# SCH_CentralkaPawela-1_3_2025-06-29.net
KiCad netlist of a schematic drawn in EasyEDA
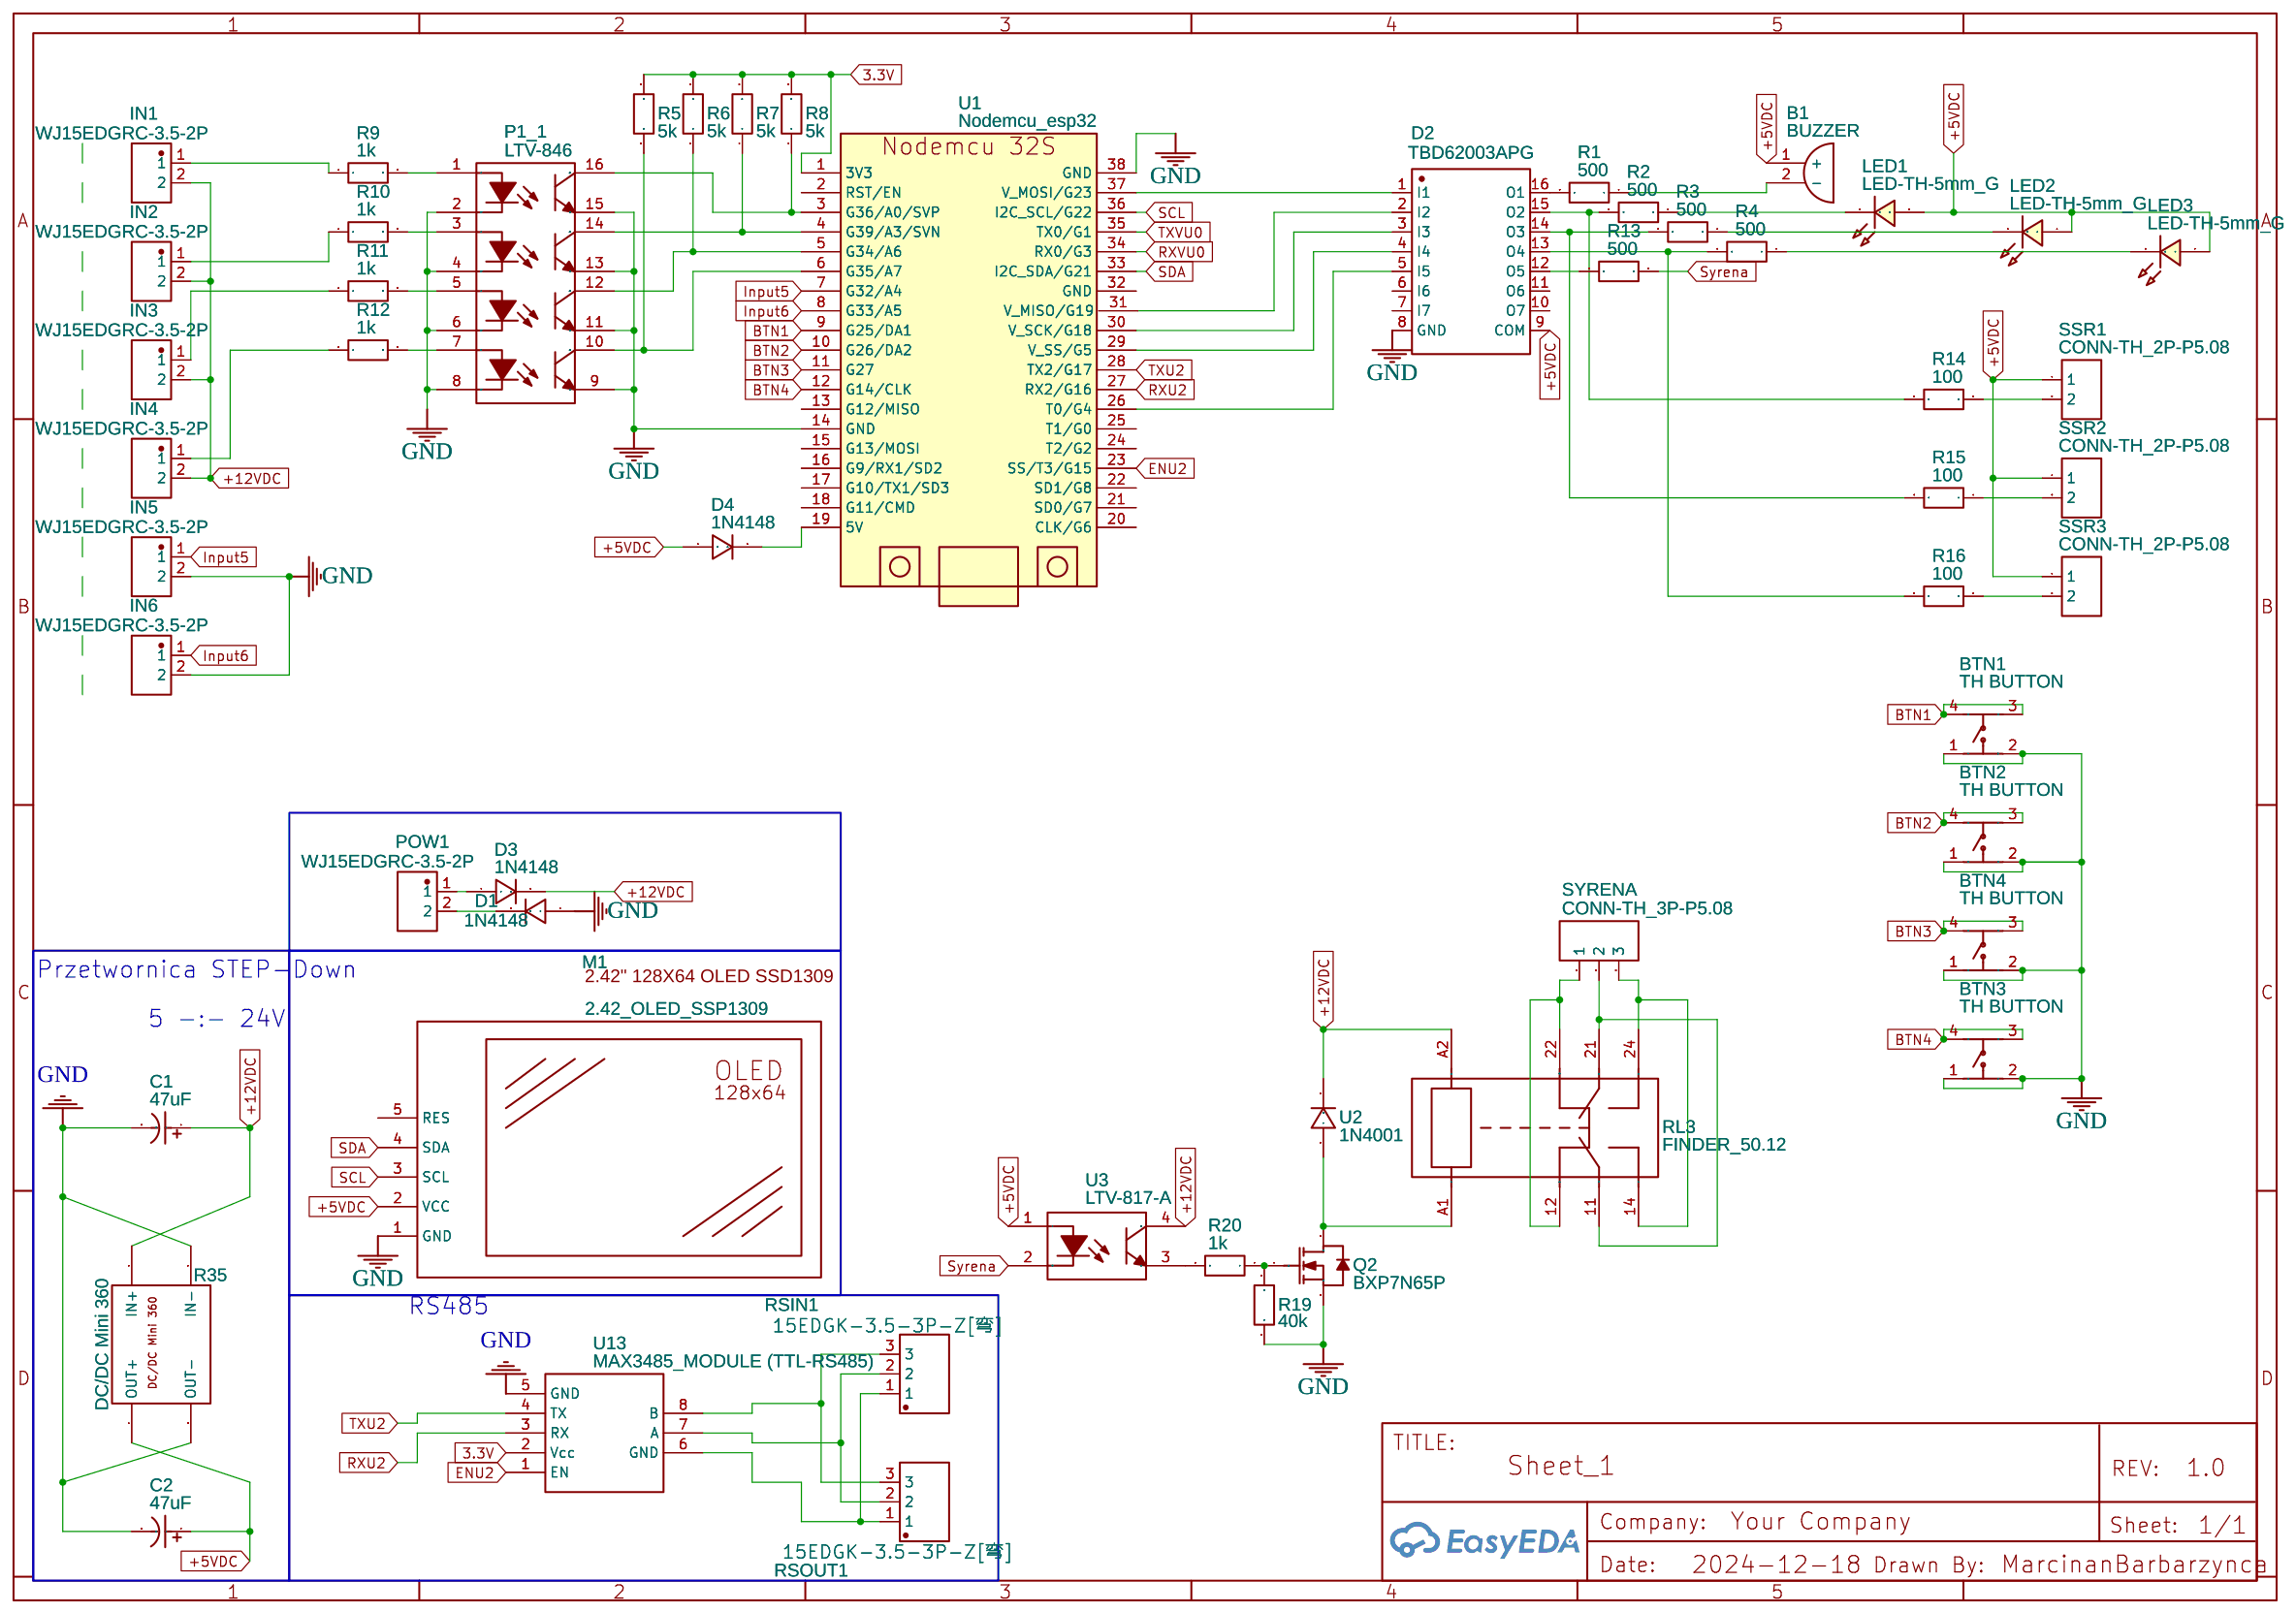
[diagram p0: schematic sheet]

(export (version "E")
  (design (tool "Eeschema 10.0.6"))
  (components
    (comp (ref "B1") (value "BUZZER") (libsource (lib "") (part "BUZZER")))
    (comp (ref "BTN1")
      (value "TH BUTTON")
      (fields (field (name "Manufacturer Part") "button6*6*8") (field (name "Manufacturer") "ReliaPro"))
      (libsource (lib "") (part "TH BUTTON"))
    )
    (comp (ref "BTN2")
      (value "TH BUTTON")
      (fields (field (name "Manufacturer Part") "button6*6*8") (field (name "Manufacturer") "ReliaPro"))
      (libsource (lib "") (part "TH BUTTON"))
    )
    (comp (ref "BTN3")
      (value "TH BUTTON")
      (fields (field (name "Manufacturer Part") "button6*6*8") (field (name "Manufacturer") "ReliaPro"))
      (libsource (lib "") (part "TH BUTTON"))
    )
    (comp (ref "BTN4")
      (value "TH BUTTON")
      (fields (field (name "Manufacturer Part") "button6*6*8") (field (name "Manufacturer") "ReliaPro"))
      (libsource (lib "") (part "TH BUTTON"))
    )
    (comp (ref "C1")
      (value "47uF")
      (fields
        (field (name "Manufacturer Part") "47uF 16V Aluminum electrolytic capacitors")
        (field (name "Manufacturer") "ValuePro")
      )
      (libsource (lib "") (part "47uF 16V Aluminum electrolytic capacitors"))
    )
    (comp (ref "C2")
      (value "47uF")
      (fields
        (field (name "Manufacturer Part") "47uF 16V Aluminum electrolytic capacitors")
        (field (name "Manufacturer") "ValuePro")
      )
      (libsource (lib "") (part "47uF 16V Aluminum electrolytic capacitors"))
    )
    (comp (ref "D1")
      (value "1N4148")
      (fields (field (name "Manufacturer") "SEMTECH"))
      (libsource (lib "") (part "1N4148_1"))
    )
    (comp (ref "D2")
      (value "TBD62003APG")
      (fields (field (name "Manufacturer") "TOSHIBA"))
      (libsource (lib "") (part "TBD62003APG"))
    )
    (comp (ref "D3")
      (value "1N4148")
      (fields (field (name "Manufacturer") "SEMTECH"))
      (libsource (lib "") (part "1N4148"))
    )
    (comp (ref "D4")
      (value "1N4148")
      (fields (field (name "Manufacturer") "SEMTECH"))
      (libsource (lib "") (part "1N4148"))
    )
    (comp (ref "IN1")
      (value "WJ15EDGRC-3.5-2P")
      (fields (field (name "Manufacturer") "KANGNEX(康奈克斯电气)"))
      (libsource (lib "") (part "WJ15EDGRC-3.5-2P_1"))
    )
    (comp (ref "IN2")
      (value "WJ15EDGRC-3.5-2P")
      (fields (field (name "Manufacturer") "KANGNEX(康奈克斯电气)"))
      (libsource (lib "") (part "WJ15EDGRC-3.5-2P_1"))
    )
    (comp (ref "IN3")
      (value "WJ15EDGRC-3.5-2P")
      (fields (field (name "Manufacturer") "KANGNEX(康奈克斯电气)"))
      (libsource (lib "") (part "WJ15EDGRC-3.5-2P_1"))
    )
    (comp (ref "IN4")
      (value "WJ15EDGRC-3.5-2P")
      (fields (field (name "Manufacturer") "KANGNEX(康奈克斯电气)"))
      (libsource (lib "") (part "WJ15EDGRC-3.5-2P_1"))
    )
    (comp (ref "IN5")
      (value "WJ15EDGRC-3.5-2P")
      (fields (field (name "Manufacturer") "KANGNEX(康奈克斯电气)"))
      (libsource (lib "") (part "WJ15EDGRC-3.5-2P_1"))
    )
    (comp (ref "IN6")
      (value "WJ15EDGRC-3.5-2P")
      (fields (field (name "Manufacturer") "KANGNEX(康奈克斯电气)"))
      (libsource (lib "") (part "WJ15EDGRC-3.5-2P_1"))
    )
    (comp (ref "LED1")
      (value "LED-TH-5mm_G")
      (fields
        (field (name "Manufacturer Part") "333-2SYGD/S530-E2")
        (field (name "Manufacturer") "EVERLIGHT(台湾亿光)")
      )
      (libsource (lib "") (part "LED-TH-5mm_G"))
    )
    (comp (ref "LED2")
      (value "LED-TH-5mm_G")
      (fields
        (field (name "Manufacturer Part") "333-2SYGD/S530-E2")
        (field (name "Manufacturer") "EVERLIGHT(台湾亿光)")
      )
      (libsource (lib "") (part "LED-TH-5mm_G"))
    )
    (comp (ref "LED3")
      (value "LED-TH-5mm_G")
      (fields
        (field (name "Manufacturer Part") "333-2SYGD/S530-E2")
        (field (name "Manufacturer") "EVERLIGHT(台湾亿光)")
      )
      (libsource (lib "") (part "LED-TH-5mm_G"))
    )
    (comp (ref "M1") (value "2.42_OLED_SSP1309") (libsource (lib "") (part "2.42_OLED_SSP1309")))
    (comp (ref "P1_1")
      (value "LTV-846")
      (fields (field (name "Manufacturer") "LITEON"))
      (libsource (lib "") (part "LTV-846"))
    )
    (comp (ref "POW1")
      (value "WJ15EDGRC-3.5-2P")
      (fields (field (name "Manufacturer") "KANGNEX(康奈克斯电气)"))
      (libsource (lib "") (part "WJ15EDGRC-3.5-2P"))
    )
    (comp (ref "Q2")
      (value "BXP7N65P")
      (fields (field (name "Manufacturer Part") "IPP60R385CP") (field (name "Manufacturer") "Infineon(英飞凌)"))
      (libsource (lib "") (part "IPP60R385CP"))
    )
    (comp (ref "R1") (value "500") (libsource (lib "") (part "R_AXIAL-0.3_EU")))
    (comp (ref "R2") (value "500") (libsource (lib "") (part "R_AXIAL-0.3_EU")))
    (comp (ref "R3") (value "500") (libsource (lib "") (part "R_AXIAL-0.3_EU")))
    (comp (ref "R4") (value "500") (libsource (lib "") (part "R_AXIAL-0.3_EU")))
    (comp (ref "R5") (value "5k") (libsource (lib "") (part "R_AXIAL-0.3_EU_2")))
    (comp (ref "R6") (value "5k") (libsource (lib "") (part "R_AXIAL-0.3_EU_2")))
    (comp (ref "R7") (value "5k") (libsource (lib "") (part "R_AXIAL-0.3_EU_2")))
    (comp (ref "R8") (value "5k") (libsource (lib "") (part "R_AXIAL-0.3_EU_2")))
    (comp (ref "R9") (value "1k") (libsource (lib "") (part "R_AXIAL-0.3_EU_1")))
    (comp (ref "R10") (value "1k") (libsource (lib "") (part "R_AXIAL-0.3_EU_1")))
    (comp (ref "R11") (value "1k") (libsource (lib "") (part "R_AXIAL-0.3_EU_1")))
    (comp (ref "R12") (value "1k") (libsource (lib "") (part "R_AXIAL-0.3_EU_1")))
    (comp (ref "R13") (value "500") (libsource (lib "") (part "R_AXIAL-0.3_EU")))
    (comp (ref "R14") (value "100") (libsource (lib "") (part "R_AXIAL-0.3_EU")))
    (comp (ref "R15") (value "100") (libsource (lib "") (part "R_AXIAL-0.3_EU")))
    (comp (ref "R16") (value "100") (libsource (lib "") (part "R_AXIAL-0.3_EU")))
    (comp (ref "R19") (value "40k") (libsource (lib "") (part "R_AXIAL-0.3_EU_3")))
    (comp (ref "R20") (value "1k") (libsource (lib "") (part "R_AXIAL-0.3_EU")))
    (comp (ref "R35") (value "DC/DC Mini 360") (libsource (lib "") (part "DC/DC Mini 360")))
    (comp (ref "RL3")
      (value "FINDER_50.12")
      (fields (field (name "Manufacturer Part") "New SchematicLib"))
      (libsource (lib "") (part "FINDER_40.52.7.012.0000"))
    )
    (comp (ref "RSIN1") (value "15EDGK-3.5-3P-Z[弯]") (libsource (lib "") (part "15EDGK-3.5-3P-Z[弯]_1")))
    (comp (ref "RSOUT1") (value "15EDGK-3.5-3P-Z[弯]") (libsource (lib "") (part "15EDGK-3.5-3P-Z[弯]")))
    (comp (ref "SSR1") (value "CONN-TH_2P-P5.08") (libsource (lib "") (part "CONN-TH_2P-P5.08")))
    (comp (ref "SSR2") (value "CONN-TH_2P-P5.08") (libsource (lib "") (part "CONN-TH_2P-P5.08")))
    (comp (ref "SSR3") (value "CONN-TH_2P-P5.08") (libsource (lib "") (part "CONN-TH_2P-P5.08")))
    (comp (ref "SYRENA") (value "CONN-TH_3P-P5.08") (libsource (lib "") (part "CONN-TH_3P-P5.08")))
    (comp (ref "U1")
      (value "Nodemcu_esp32")
      (fields (field (name "Manufacturer Part") "Nodemcu esp32"))
      (libsource (lib "") (part "Nodemcu_esp32"))
    )
    (comp (ref "U2")
      (value "1N4001")
      (fields (field (name "Manufacturer") "HL(豪林)"))
      (libsource (lib "") (part "1N4001_C237252"))
    )
    (comp (ref "U3")
      (value "LTV-817-A")
      (fields (field (name "Manufacturer") "LITEON(光宝)"))
      (libsource (lib "") (part "LTV-817-A"))
    )
    (comp (ref "U13")
      (value "MAX3485_MODULE (TTL-RS485)")
      (libsource (lib "") (part "MAX3485_MODULE (TTL-RS485)"))
    )
  )
  (nets
    (net (code "1") (name "+5VDC") (class "Default")
      (node (ref "B1") (pin "1") (pinfunction "+_1") (pintype "unspecified"))
      (node (ref "C2") (pin "1") (pinfunction "1_1") (pintype "input"))
      (node (ref "D2") (pin "9") (pinfunction "COM_9") (pintype "unspecified"))
      (node (ref "D4") (pin "1") (pinfunction "1_1") (pintype "unspecified"))
      (node (ref "LED1") (pin "1") (pinfunction "1_1") (pintype "unspecified"))
      (node (ref "LED2") (pin "1") (pinfunction "1_1") (pintype "unspecified"))
      (node (ref "LED3") (pin "1") (pinfunction "1_1") (pintype "unspecified"))
      (node (ref "M1") (pin "2") (pinfunction "VCC_2") (pintype "unspecified"))
      (node (ref "R35") (pin "4") (pinfunction "OUT+_4") (pintype "unspecified"))
      (node (ref "SSR1") (pin "1") (pinfunction "1_1") (pintype "unspecified"))
      (node (ref "SSR2") (pin "1") (pinfunction "1_1") (pintype "unspecified"))
      (node (ref "SSR3") (pin "1") (pinfunction "1_1") (pintype "unspecified"))
      (node (ref "U3") (pin "1") (pinfunction "AN_1") (pintype "unspecified"))
    )
    (net (code "2") (name "+12VDC") (class "Default")
      (node (ref "C1") (pin "1") (pinfunction "1_1") (pintype "input"))
      (node (ref "D3") (pin "2") (pinfunction "2_2") (pintype "unspecified"))
      (node (ref "IN1") (pin "2") (pinfunction "2_2") (pintype "unspecified"))
      (node (ref "IN2") (pin "2") (pinfunction "2_2") (pintype "unspecified"))
      (node (ref "IN3") (pin "2") (pinfunction "2_2") (pintype "unspecified"))
      (node (ref "IN4") (pin "2") (pinfunction "2_2") (pintype "unspecified"))
      (node (ref "R35") (pin "1") (pinfunction "IN+_1") (pintype "unspecified"))
      (node (ref "RL3") (pin "A2") (pinfunction "A2_A2") (pintype "unspecified"))
      (node (ref "U2") (pin "1") (pinfunction "C_1") (pintype "unspecified"))
      (node (ref "U3") (pin "4") (pinfunction "COL_4") (pintype "unspecified"))
    )
    (net (code "3") (name "3.3V") (class "Default")
      (node (ref "R5") (pin "2") (pinfunction "2_2") (pintype "unspecified"))
      (node (ref "R6") (pin "2") (pinfunction "2_2") (pintype "unspecified"))
      (node (ref "R7") (pin "2") (pinfunction "2_2") (pintype "unspecified"))
      (node (ref "R8") (pin "2") (pinfunction "2_2") (pintype "unspecified"))
      (node (ref "U1") (pin "1") (pinfunction "3V3_1") (pintype "passive"))
      (node (ref "U13") (pin "2") (pinfunction "Vcc_2") (pintype "unspecified"))
    )
    (net (code "4") (name "BTN1") (class "Default")
      (node (ref "BTN1") (pin "3") (pinfunction "3_3") (pintype "unspecified"))
      (node (ref "BTN1") (pin "4") (pinfunction "4_4") (pintype "unspecified"))
      (node (ref "U1") (pin "9") (pinfunction "G25/DA1_9") (pintype "bidirectional"))
    )
    (net (code "5") (name "BTN2") (class "Default")
      (node (ref "BTN2") (pin "3") (pinfunction "3_3") (pintype "unspecified"))
      (node (ref "BTN2") (pin "4") (pinfunction "4_4") (pintype "unspecified"))
      (node (ref "U1") (pin "10") (pinfunction "G26/DA2_10") (pintype "bidirectional"))
    )
    (net (code "6") (name "BTN3") (class "Default")
      (node (ref "BTN4") (pin "3") (pinfunction "3_3") (pintype "unspecified"))
      (node (ref "BTN4") (pin "4") (pinfunction "4_4") (pintype "unspecified"))
      (node (ref "U1") (pin "11") (pinfunction "G27_11") (pintype "bidirectional"))
    )
    (net (code "7") (name "BTN4") (class "Default")
      (node (ref "BTN3") (pin "3") (pinfunction "3_3") (pintype "unspecified"))
      (node (ref "BTN3") (pin "4") (pinfunction "4_4") (pintype "unspecified"))
      (node (ref "U1") (pin "12") (pinfunction "G14/CLK_12") (pintype "bidirectional"))
    )
    (net (code "8") (name "ENU2") (class "Default")
      (node (ref "U1") (pin "23") (pinfunction "SS/T3/G15_23") (pintype "bidirectional"))
      (node (ref "U13") (pin "1") (pinfunction "EN_1") (pintype "unspecified"))
    )
    (net (code "9") (name "GND") (class "Default")
      (node (ref "BTN1") (pin "1") (pinfunction "1_1") (pintype "unspecified"))
      (node (ref "BTN1") (pin "2") (pinfunction "2_2") (pintype "unspecified"))
      (node (ref "BTN2") (pin "1") (pinfunction "1_1") (pintype "unspecified"))
      (node (ref "BTN2") (pin "2") (pinfunction "2_2") (pintype "unspecified"))
      (node (ref "BTN3") (pin "1") (pinfunction "1_1") (pintype "unspecified"))
      (node (ref "BTN3") (pin "2") (pinfunction "2_2") (pintype "unspecified"))
      (node (ref "BTN4") (pin "1") (pinfunction "1_1") (pintype "unspecified"))
      (node (ref "BTN4") (pin "2") (pinfunction "2_2") (pintype "unspecified"))
      (node (ref "C1") (pin "2") (pinfunction "2_2") (pintype "input"))
      (node (ref "C2") (pin "2") (pinfunction "2_2") (pintype "input"))
      (node (ref "D1") (pin "1") (pinfunction "1_1") (pintype "unspecified"))
      (node (ref "D2") (pin "8") (pinfunction "GND_8") (pintype "unspecified"))
      (node (ref "IN5") (pin "2") (pinfunction "2_2") (pintype "unspecified"))
      (node (ref "IN6") (pin "2") (pinfunction "2_2") (pintype "unspecified"))
      (node (ref "M1") (pin "1") (pinfunction "GND_1") (pintype "unspecified"))
      (node (ref "P1_1") (pin "11") (pinfunction "EM_11") (pintype "unspecified"))
      (node (ref "P1_1") (pin "13") (pinfunction "EM_13") (pintype "unspecified"))
      (node (ref "P1_1") (pin "15") (pinfunction "EM_15") (pintype "unspecified"))
      (node (ref "P1_1") (pin "2") (pinfunction "CAT_2") (pintype "unspecified"))
      (node (ref "P1_1") (pin "4") (pinfunction "CAT_4") (pintype "unspecified"))
      (node (ref "P1_1") (pin "6") (pinfunction "CAT_6") (pintype "unspecified"))
      (node (ref "P1_1") (pin "8") (pinfunction "CAT_8") (pintype "unspecified"))
      (node (ref "P1_1") (pin "9") (pinfunction "EM_9") (pintype "unspecified"))
      (node (ref "Q2") (pin "3") (pinfunction "S_3") (pintype "unspecified"))
      (node (ref "R19") (pin "2") (pinfunction "2_2") (pintype "unspecified"))
      (node (ref "R35") (pin "2") (pinfunction "IN-_2") (pintype "unspecified"))
      (node (ref "R35") (pin "3") (pinfunction "OUT-_3") (pintype "unspecified"))
      (node (ref "U1") (pin "14") (pinfunction "GND_14") (pintype "passive"))
      (node (ref "U1") (pin "38") (pinfunction "GND_38") (pintype "passive"))
      (node (ref "U13") (pin "5") (pinfunction "GND_5") (pintype "unspecified"))
    )
    (net (code "10") (name "Input5") (class "Default")
      (node (ref "IN5") (pin "1") (pinfunction "1_1") (pintype "unspecified"))
      (node (ref "U1") (pin "7") (pinfunction "G32/A4_7") (pintype "bidirectional"))
    )
    (net (code "11") (name "Input6") (class "Default")
      (node (ref "IN6") (pin "1") (pinfunction "1_1") (pintype "unspecified"))
      (node (ref "U1") (pin "8") (pinfunction "G33/A5_8") (pintype "bidirectional"))
    )
    (net (code "12") (name "Net-(B1--)") (class "Default")
      (node (ref "B1") (pin "2") (pinfunction "-_2") (pintype "unspecified"))
      (node (ref "R1") (pin "1") (pinfunction "1_1") (pintype "unspecified"))
    )
    (net (code "13") (name "Net-(D1-Pad2)") (class "Default")
      (node (ref "D1") (pin "2") (pinfunction "2_2") (pintype "unspecified"))
      (node (ref "POW1") (pin "2") (pinfunction "2_2") (pintype "unspecified"))
    )
    (net (code "14") (name "Net-(D2-I1)") (class "Default")
      (node (ref "D2") (pin "1") (pinfunction "I1_1") (pintype "unspecified"))
      (node (ref "U1") (pin "37") (pinfunction "V_MOSI/G23_37") (pintype "bidirectional"))
    )
    (net (code "15") (name "Net-(D2-I2)") (class "Default")
      (node (ref "D2") (pin "2") (pinfunction "I2_2") (pintype "unspecified"))
      (node (ref "U1") (pin "31") (pinfunction "V_MISO/G19_31") (pintype "bidirectional"))
    )
    (net (code "16") (name "Net-(D2-I3)") (class "Default")
      (node (ref "D2") (pin "3") (pinfunction "I3_3") (pintype "unspecified"))
      (node (ref "U1") (pin "30") (pinfunction "V_SCK/G18_30") (pintype "bidirectional"))
    )
    (net (code "17") (name "Net-(D2-I4)") (class "Default")
      (node (ref "D2") (pin "4") (pinfunction "I4_4") (pintype "unspecified"))
      (node (ref "U1") (pin "29") (pinfunction "V_SS/G5_29") (pintype "bidirectional"))
    )
    (net (code "18") (name "Net-(D2-I5)") (class "Default")
      (node (ref "D2") (pin "5") (pinfunction "I5_5") (pintype "unspecified"))
      (node (ref "U1") (pin "26") (pinfunction "T0/G4_26") (pintype "bidirectional"))
    )
    (net (code "19") (name "Net-(D2-O1)") (class "Default")
      (node (ref "D2") (pin "16") (pinfunction "O1_16") (pintype "unspecified"))
      (node (ref "R1") (pin "2") (pinfunction "2_2") (pintype "unspecified"))
    )
    (net (code "20") (name "Net-(D2-O2)") (class "Default")
      (node (ref "D2") (pin "15") (pinfunction "O2_15") (pintype "unspecified"))
      (node (ref "R14") (pin "2") (pinfunction "2_2") (pintype "unspecified"))
      (node (ref "R2") (pin "2") (pinfunction "2_2") (pintype "unspecified"))
    )
    (net (code "21") (name "Net-(D2-O3)") (class "Default")
      (node (ref "D2") (pin "14") (pinfunction "O3_14") (pintype "unspecified"))
      (node (ref "R15") (pin "2") (pinfunction "2_2") (pintype "unspecified"))
      (node (ref "R3") (pin "2") (pinfunction "2_2") (pintype "unspecified"))
    )
    (net (code "22") (name "Net-(D2-O4)") (class "Default")
      (node (ref "D2") (pin "13") (pinfunction "O4_13") (pintype "unspecified"))
      (node (ref "R16") (pin "2") (pinfunction "2_2") (pintype "unspecified"))
      (node (ref "R4") (pin "2") (pinfunction "2_2") (pintype "unspecified"))
    )
    (net (code "23") (name "Net-(D2-O5)") (class "Default")
      (node (ref "D2") (pin "12") (pinfunction "O5_12") (pintype "unspecified"))
      (node (ref "R13") (pin "2") (pinfunction "2_2") (pintype "unspecified"))
    )
    (net (code "24") (name "Net-(D3-Pad1)") (class "Default")
      (node (ref "D3") (pin "1") (pinfunction "1_1") (pintype "unspecified"))
      (node (ref "POW1") (pin "1") (pinfunction "1_1") (pintype "unspecified"))
    )
    (net (code "25") (name "Net-(IN1-Pad1)") (class "Default")
      (node (ref "IN1") (pin "1") (pinfunction "1_1") (pintype "unspecified"))
      (node (ref "R9") (pin "1") (pinfunction "1_1") (pintype "unspecified"))
    )
    (net (code "26") (name "Net-(IN2-Pad1)") (class "Default")
      (node (ref "IN2") (pin "1") (pinfunction "1_1") (pintype "unspecified"))
      (node (ref "R10") (pin "1") (pinfunction "1_1") (pintype "unspecified"))
    )
    (net (code "27") (name "Net-(IN3-Pad1)") (class "Default")
      (node (ref "IN3") (pin "1") (pinfunction "1_1") (pintype "unspecified"))
      (node (ref "R11") (pin "1") (pinfunction "1_1") (pintype "unspecified"))
    )
    (net (code "28") (name "Net-(IN4-Pad1)") (class "Default")
      (node (ref "IN4") (pin "1") (pinfunction "1_1") (pintype "unspecified"))
      (node (ref "R12") (pin "1") (pinfunction "1_1") (pintype "unspecified"))
    )
    (net (code "29") (name "Net-(LED1-Pad2)") (class "Default")
      (node (ref "LED1") (pin "2") (pinfunction "2_2") (pintype "unspecified"))
      (node (ref "R2") (pin "1") (pinfunction "1_1") (pintype "unspecified"))
    )
    (net (code "30") (name "Net-(LED2-Pad2)") (class "Default")
      (node (ref "LED2") (pin "2") (pinfunction "2_2") (pintype "unspecified"))
      (node (ref "R3") (pin "1") (pinfunction "1_1") (pintype "unspecified"))
    )
    (net (code "31") (name "Net-(LED3-Pad2)") (class "Default")
      (node (ref "LED3") (pin "2") (pinfunction "2_2") (pintype "unspecified"))
      (node (ref "R4") (pin "1") (pinfunction "1_1") (pintype "unspecified"))
    )
    (net (code "32") (name "Net-(P1_1-AN-Pad1)") (class "Default")
      (node (ref "P1_1") (pin "1") (pinfunction "AN_1") (pintype "unspecified"))
      (node (ref "R9") (pin "2") (pinfunction "2_2") (pintype "unspecified"))
    )
    (net (code "33") (name "Net-(P1_1-AN-Pad3)") (class "Default")
      (node (ref "P1_1") (pin "3") (pinfunction "AN_3") (pintype "unspecified"))
      (node (ref "R10") (pin "2") (pinfunction "2_2") (pintype "unspecified"))
    )
    (net (code "34") (name "Net-(P1_1-AN-Pad5)") (class "Default")
      (node (ref "P1_1") (pin "5") (pinfunction "AN_5") (pintype "unspecified"))
      (node (ref "R11") (pin "2") (pinfunction "2_2") (pintype "unspecified"))
    )
    (net (code "35") (name "Net-(P1_1-AN-Pad7)") (class "Default")
      (node (ref "P1_1") (pin "7") (pinfunction "AN_7") (pintype "unspecified"))
      (node (ref "R12") (pin "2") (pinfunction "2_2") (pintype "unspecified"))
    )
    (net (code "36") (name "Net-(Q2-D)") (class "Default")
      (node (ref "Q2") (pin "2") (pinfunction "D_2") (pintype "unspecified"))
      (node (ref "RL3") (pin "A1") (pinfunction "A1_A1") (pintype "unspecified"))
      (node (ref "U2") (pin "2") (pinfunction "A_2") (pintype "unspecified"))
    )
    (net (code "37") (name "Net-(Q2-G)") (class "Default")
      (node (ref "Q2") (pin "1") (pinfunction "G_1") (pintype "unspecified"))
      (node (ref "R19") (pin "1") (pinfunction "1_1") (pintype "unspecified"))
      (node (ref "R20") (pin "1") (pinfunction "1_1") (pintype "unspecified"))
    )
    (net (code "38") (name "Net-(R14-Pad1)") (class "Default")
      (node (ref "R14") (pin "1") (pinfunction "1_1") (pintype "unspecified"))
      (node (ref "SSR1") (pin "2") (pinfunction "2_2") (pintype "unspecified"))
    )
    (net (code "39") (name "Net-(R15-Pad1)") (class "Default")
      (node (ref "R15") (pin "1") (pinfunction "1_1") (pintype "unspecified"))
      (node (ref "SSR2") (pin "2") (pinfunction "2_2") (pintype "unspecified"))
    )
    (net (code "40") (name "Net-(R16-Pad1)") (class "Default")
      (node (ref "R16") (pin "1") (pinfunction "1_1") (pintype "unspecified"))
      (node (ref "SSR3") (pin "2") (pinfunction "2_2") (pintype "unspecified"))
    )
    (net (code "41") (name "Net-(RL3-Pad11)") (class "Default")
      (node (ref "RL3") (pin "11") (pinfunction "11_11") (pintype "unspecified"))
      (node (ref "RL3") (pin "21") (pinfunction "21_21") (pintype "unspecified"))
      (node (ref "SYRENA") (pin "2") (pinfunction "2_2") (pintype "unspecified"))
    )
    (net (code "42") (name "Net-(RL3-Pad12)") (class "Default")
      (node (ref "RL3") (pin "12") (pinfunction "12_12") (pintype "unspecified"))
      (node (ref "RL3") (pin "22") (pinfunction "22_22") (pintype "unspecified"))
      (node (ref "SYRENA") (pin "1") (pinfunction "1_1") (pintype "unspecified"))
    )
    (net (code "43") (name "Net-(RL3-Pad14)") (class "Default")
      (node (ref "RL3") (pin "14") (pinfunction "14_14") (pintype "unspecified"))
      (node (ref "RL3") (pin "24") (pinfunction "24_24") (pintype "unspecified"))
      (node (ref "SYRENA") (pin "3") (pinfunction "3_3") (pintype "unspecified"))
    )
    (net (code "44") (name "Net-(RSIN1-Pad1)") (class "Default")
      (node (ref "RSIN1") (pin "1") (pinfunction "1_1") (pintype "unspecified"))
      (node (ref "RSOUT1") (pin "1") (pinfunction "1_1") (pintype "unspecified"))
      (node (ref "U13") (pin "6") (pinfunction "GND_6") (pintype "unspecified"))
    )
    (net (code "45") (name "Net-(U1-5V)") (class "Default")
      (node (ref "D4") (pin "2") (pinfunction "2_2") (pintype "unspecified"))
      (node (ref "U1") (pin "19") (pinfunction "5V_19") (pintype "passive"))
    )
    (net (code "46") (name "Net-(U1-G34{slash}A6)") (class "Default")
      (node (ref "P1_1") (pin "12") (pinfunction "COL_12") (pintype "unspecified"))
      (node (ref "R6") (pin "1") (pinfunction "1_1") (pintype "unspecified"))
      (node (ref "U1") (pin "5") (pinfunction "G34/A6_5") (pintype "bidirectional"))
    )
    (net (code "47") (name "Net-(U1-G35{slash}A7)") (class "Default")
      (node (ref "P1_1") (pin "10") (pinfunction "COL_10") (pintype "unspecified"))
      (node (ref "R5") (pin "1") (pinfunction "1_1") (pintype "unspecified"))
      (node (ref "U1") (pin "6") (pinfunction "G35/A7_6") (pintype "bidirectional"))
    )
    (net (code "48") (name "Net-(U1-G36{slash}A0{slash}SVP)") (class "Default")
      (node (ref "P1_1") (pin "16") (pinfunction "COL_16") (pintype "unspecified"))
      (node (ref "R8") (pin "1") (pinfunction "1_1") (pintype "unspecified"))
      (node (ref "U1") (pin "3") (pinfunction "G36/A0/SVP_3") (pintype "bidirectional"))
    )
    (net (code "49") (name "Net-(U1-G39{slash}A3{slash}SVN)") (class "Default")
      (node (ref "P1_1") (pin "14") (pinfunction "COL_14") (pintype "unspecified"))
      (node (ref "R7") (pin "1") (pinfunction "1_1") (pintype "unspecified"))
      (node (ref "U1") (pin "4") (pinfunction "G39/A3/SVN_4") (pintype "bidirectional"))
    )
    (net (code "50") (name "Net-(U3-EM)") (class "Default")
      (node (ref "R20") (pin "2") (pinfunction "2_2") (pintype "unspecified"))
      (node (ref "U3") (pin "3") (pinfunction "EM_3") (pintype "unspecified"))
    )
    (net (code "51") (name "Net-(U13-A)") (class "Default")
      (node (ref "RSIN1") (pin "2") (pinfunction "2_2") (pintype "unspecified"))
      (node (ref "RSOUT1") (pin "2") (pinfunction "2_2") (pintype "unspecified"))
      (node (ref "U13") (pin "7") (pinfunction "A_7") (pintype "unspecified"))
    )
    (net (code "52") (name "Net-(U13-B)") (class "Default")
      (node (ref "RSIN1") (pin "3") (pinfunction "3_3") (pintype "unspecified"))
      (node (ref "RSOUT1") (pin "3") (pinfunction "3_3") (pintype "unspecified"))
      (node (ref "U13") (pin "8") (pinfunction "B_8") (pintype "unspecified"))
    )
    (net (code "53") (name "RXU2") (class "Default")
      (node (ref "U1") (pin "27") (pinfunction "RX2/G16_27") (pintype "bidirectional"))
      (node (ref "U13") (pin "3") (pinfunction "RX_3") (pintype "unspecified"))
    )
    (net (code "54") (name "RXVU0") (class "Default")
      (node (ref "U1") (pin "34") (pinfunction "RX0/G3_34") (pintype "bidirectional"))
    )
    (net (code "55") (name "SCL") (class "Default")
      (node (ref "M1") (pin "3") (pinfunction "SCL_3") (pintype "unspecified"))
      (node (ref "U1") (pin "36") (pinfunction "I2C_SCL/G22_36") (pintype "bidirectional"))
    )
    (net (code "56") (name "SDA") (class "Default")
      (node (ref "M1") (pin "4") (pinfunction "SDA_4") (pintype "unspecified"))
      (node (ref "U1") (pin "33") (pinfunction "I2C_SDA/G21_33") (pintype "bidirectional"))
    )
    (net (code "57") (name "Syrena") (class "Default")
      (node (ref "R13") (pin "1") (pinfunction "1_1") (pintype "unspecified"))
      (node (ref "U3") (pin "2") (pinfunction "CAT_2") (pintype "unspecified"))
    )
    (net (code "58") (name "TXU2") (class "Default")
      (node (ref "U1") (pin "28") (pinfunction "TX2/G17_28") (pintype "bidirectional"))
      (node (ref "U13") (pin "4") (pinfunction "TX_4") (pintype "unspecified"))
    )
    (net (code "59") (name "TXVU0") (class "Default")
      (node (ref "U1") (pin "35") (pinfunction "TX0/G1_35") (pintype "bidirectional"))
    )
    (net (code "60") (name "unconnected-(D2-I6-Pad6)") (class "Default")
      (node (ref "D2") (pin "6") (pinfunction "I6_6") (pintype "unspecified"))
    )
    (net (code "61") (name "unconnected-(D2-I7-Pad7)") (class "Default")
      (node (ref "D2") (pin "7") (pinfunction "I7_7") (pintype "unspecified"))
    )
    (net (code "62") (name "unconnected-(D2-O6-Pad11)") (class "Default")
      (node (ref "D2") (pin "11") (pinfunction "O6_11") (pintype "unspecified"))
    )
    (net (code "63") (name "unconnected-(D2-O7-Pad10)") (class "Default")
      (node (ref "D2") (pin "10") (pinfunction "O7_10") (pintype "unspecified"))
    )
    (net (code "64") (name "unconnected-(M1-RES-Pad5)") (class "Default")
      (node (ref "M1") (pin "5") (pinfunction "RES_5") (pintype "unspecified"))
    )
    (net (code "65") (name "unconnected-(U1-CLK{slash}G6-Pad20)") (class "Default")
      (node (ref "U1") (pin "20") (pinfunction "CLK/G6_20") (pintype "bidirectional"))
    )
    (net (code "66") (name "unconnected-(U1-G9{slash}RX1{slash}SD2-Pad16)") (class "Default")
      (node (ref "U1") (pin "16") (pinfunction "G9/RX1/SD2_16") (pintype "bidirectional"))
    )
    (net (code "67") (name "unconnected-(U1-G10{slash}TX1{slash}SD3-Pad17)") (class "Default")
      (node (ref "U1") (pin "17") (pinfunction "G10/TX1/SD3_17") (pintype "bidirectional"))
    )
    (net (code "68") (name "unconnected-(U1-G11{slash}CMD-Pad18)") (class "Default")
      (node (ref "U1") (pin "18") (pinfunction "G11/CMD_18") (pintype "bidirectional"))
    )
    (net (code "69") (name "unconnected-(U1-G12{slash}MISO-Pad13)") (class "Default")
      (node (ref "U1") (pin "13") (pinfunction "G12/MISO_13") (pintype "bidirectional"))
    )
    (net (code "70") (name "unconnected-(U1-G13{slash}MOSI-Pad15)") (class "Default")
      (node (ref "U1") (pin "15") (pinfunction "G13/MOSI_15") (pintype "bidirectional"))
    )
    (net (code "71") (name "unconnected-(U1-GND-Pad32)") (class "Default")
      (node (ref "U1") (pin "32") (pinfunction "GND_32") (pintype "passive"))
    )
    (net (code "72") (name "unconnected-(U1-RST{slash}EN-Pad2)") (class "Default")
      (node (ref "U1") (pin "2") (pinfunction "RST/EN_2") (pintype "bidirectional"))
    )
    (net (code "73") (name "unconnected-(U1-SD0{slash}G7-Pad21)") (class "Default")
      (node (ref "U1") (pin "21") (pinfunction "SD0/G7_21") (pintype "bidirectional"))
    )
    (net (code "74") (name "unconnected-(U1-SD1{slash}G8-Pad22)") (class "Default")
      (node (ref "U1") (pin "22") (pinfunction "SD1/G8_22") (pintype "bidirectional"))
    )
    (net (code "75") (name "unconnected-(U1-T1{slash}G0-Pad25)") (class "Default")
      (node (ref "U1") (pin "25") (pinfunction "T1/G0_25") (pintype "bidirectional"))
    )
    (net (code "76") (name "unconnected-(U1-T2{slash}G2-Pad24)") (class "Default")
      (node (ref "U1") (pin "24") (pinfunction "T2/G2_24") (pintype "bidirectional"))
    )
  )
)
